# SCH_MCP23017_usb_to_ttl_2021-07-08.net
KiCad netlist of a schematic drawn in EasyEDA
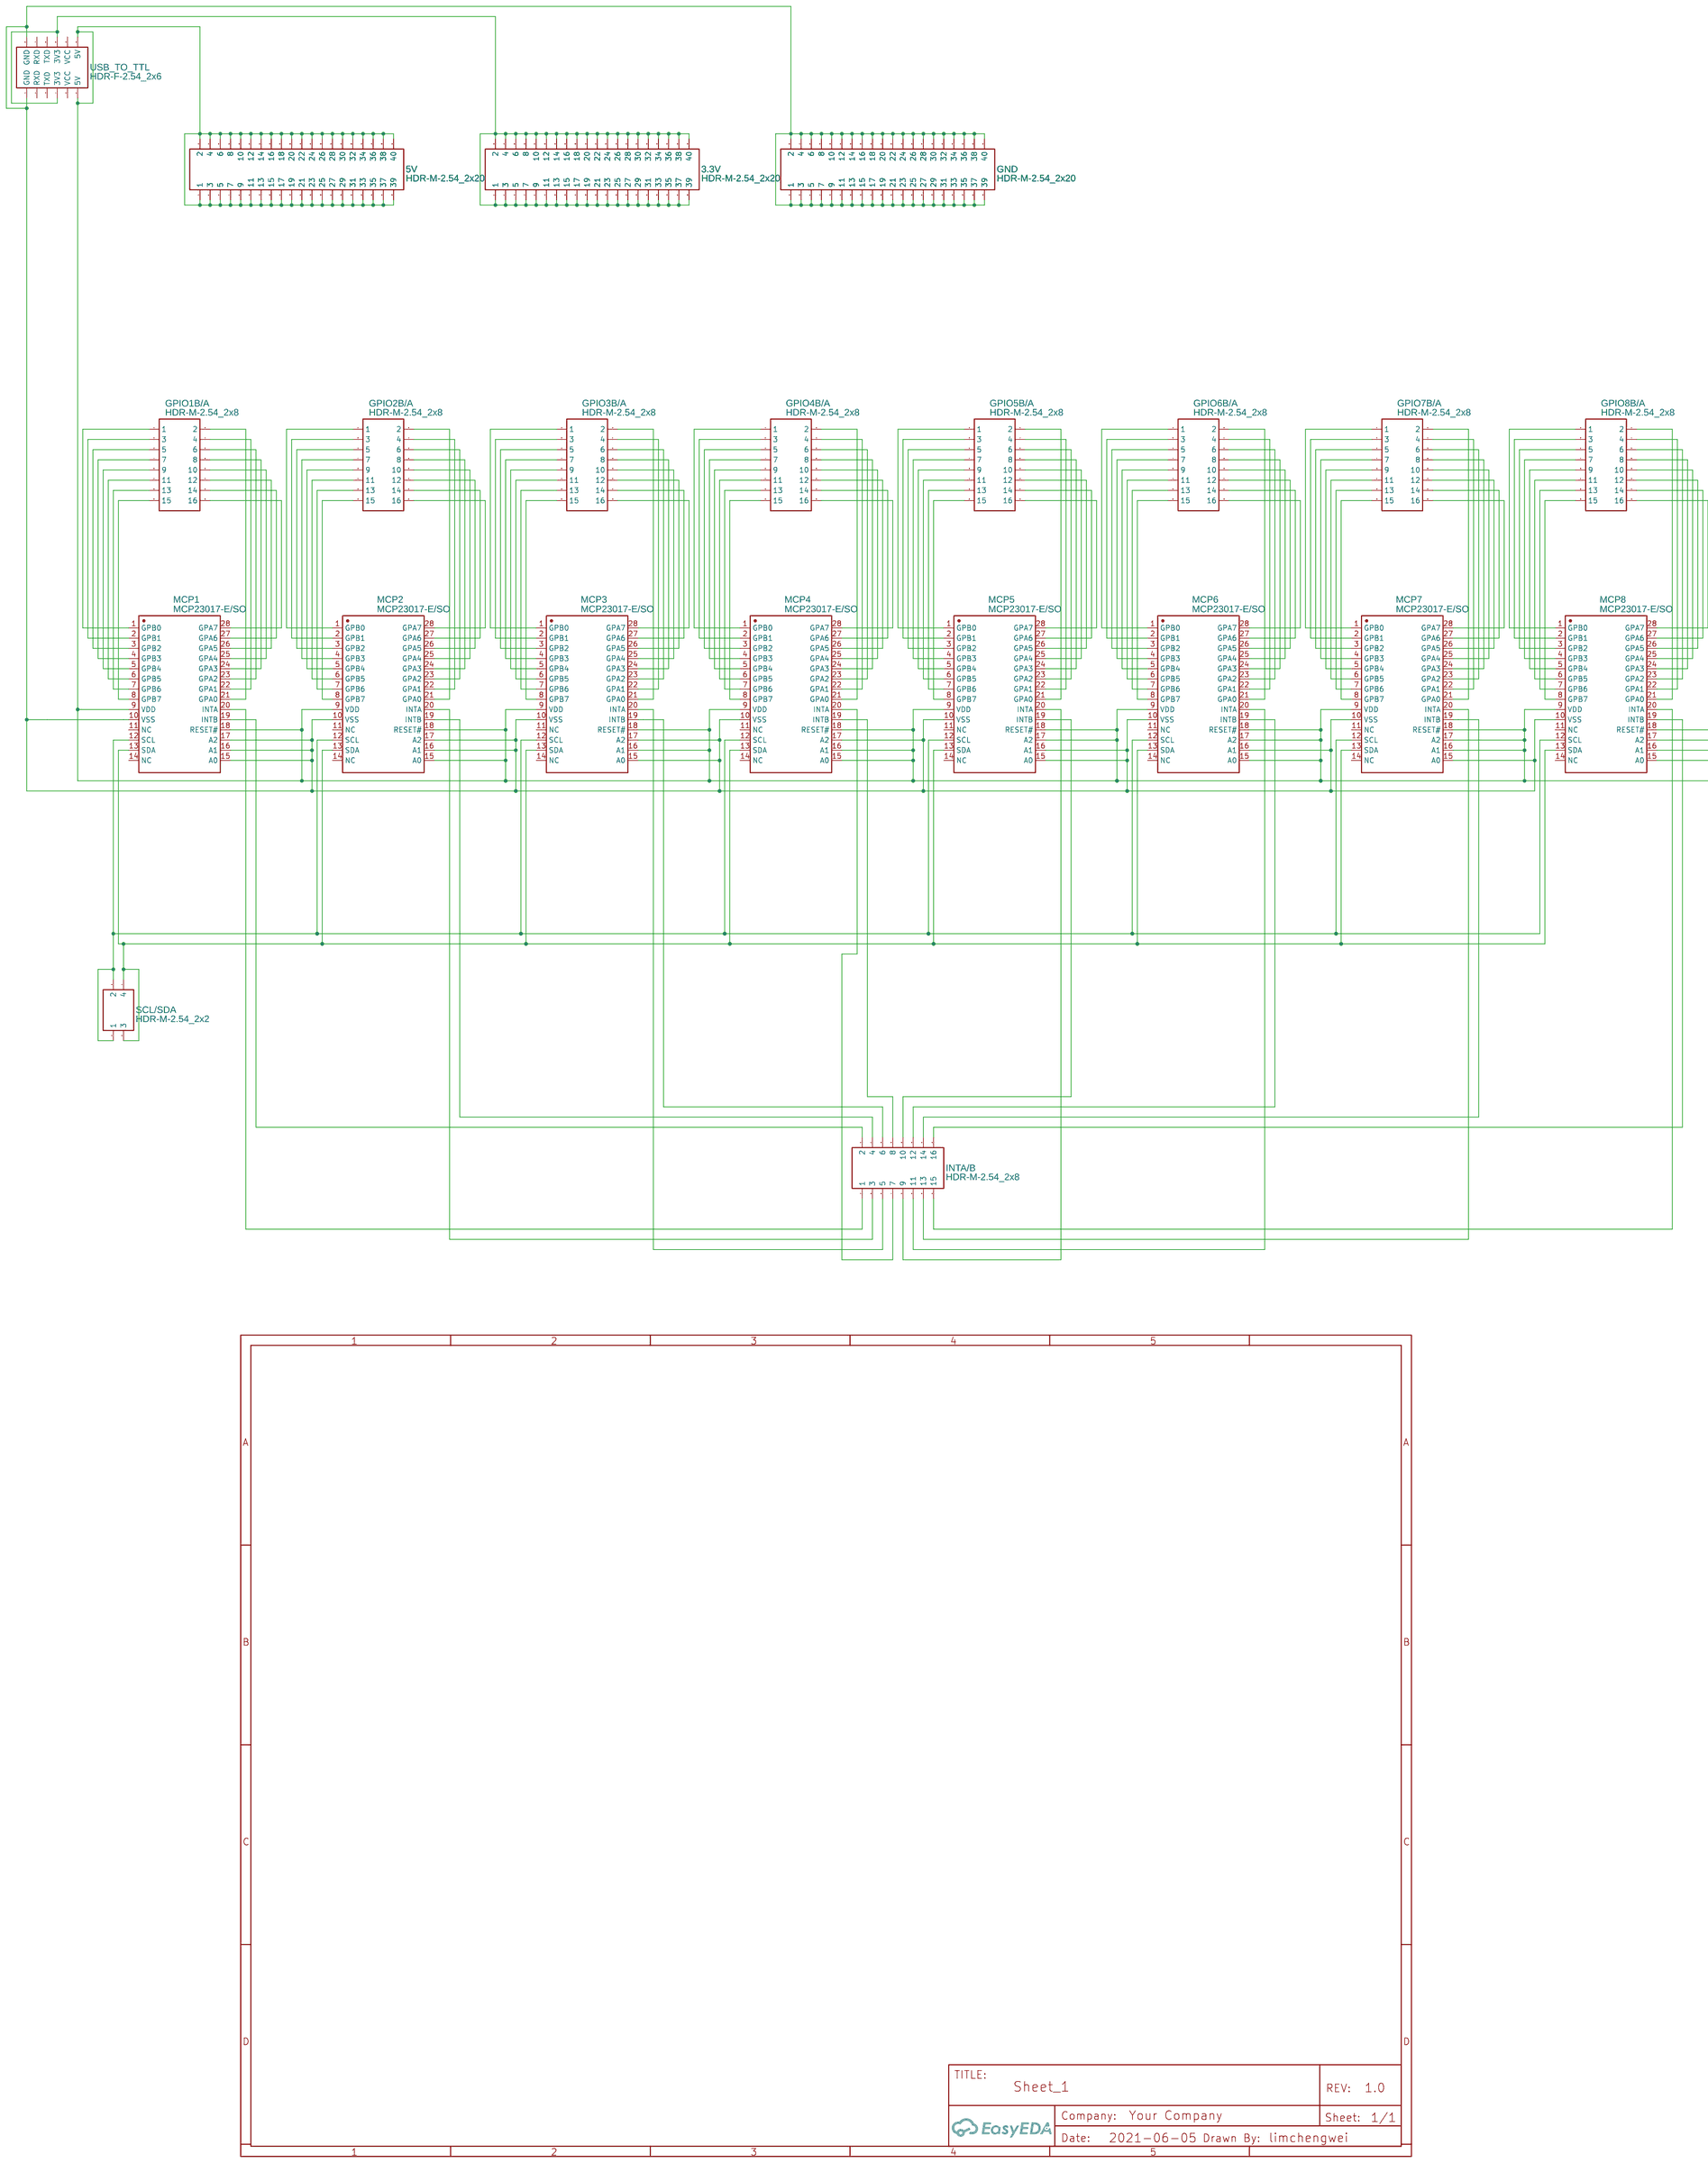
[diagram p0: schematic sheet]

(export (version "E")
  (design (tool "Eeschema 10.0.6"))
  (components
    (comp (ref "3.3V")
      (value "HDR-M-2.54_2x20")
      (fields (field (name "BOM_Supplier Part") "C50980"))
      (libsource (lib "") (part "HDR-M-2.54_2x20"))
    )
    (comp (ref "5V")
      (value "HDR-M-2.54_2x20")
      (fields (field (name "BOM_Supplier Part") "C50980"))
      (libsource (lib "") (part "HDR-M-2.54_2x20_1"))
    )
    (comp (ref "GND")
      (value "HDR-M-2.54_2x20")
      (fields (field (name "BOM_Supplier Part") "C50980"))
      (libsource (lib "") (part "HDR-M-2.54_2x20_2"))
    )
    (comp (ref "GPIO1B/A")
      (value "HDR-M-2.54_2x8")
      (fields (field (name "BOM_Supplier Part") "C68234"))
      (libsource (lib "") (part "HDR-M-2.54_2x8_8"))
    )
    (comp (ref "GPIO2B/A")
      (value "HDR-M-2.54_2x8")
      (fields (field (name "BOM_Supplier Part") "C68234"))
      (libsource (lib "") (part "HDR-M-2.54_2x8_2"))
    )
    (comp (ref "GPIO3B/A")
      (value "HDR-M-2.54_2x8")
      (fields (field (name "BOM_Supplier Part") "C68234"))
      (libsource (lib "") (part "HDR-M-2.54_2x8"))
    )
    (comp (ref "GPIO4B/A")
      (value "HDR-M-2.54_2x8")
      (fields (field (name "BOM_Supplier Part") "C68234"))
      (libsource (lib "") (part "HDR-M-2.54_2x8_4"))
    )
    (comp (ref "GPIO5B/A")
      (value "HDR-M-2.54_2x8")
      (fields (field (name "BOM_Supplier Part") "C68234"))
      (libsource (lib "") (part "HDR-M-2.54_2x8_6"))
    )
    (comp (ref "GPIO6B/A")
      (value "HDR-M-2.54_2x8")
      (fields (field (name "BOM_Supplier Part") "C68234"))
      (libsource (lib "") (part "HDR-M-2.54_2x8_3"))
    )
    (comp (ref "GPIO7B/A")
      (value "HDR-M-2.54_2x8")
      (fields (field (name "BOM_Supplier Part") "C68234"))
      (libsource (lib "") (part "HDR-M-2.54_2x8_5"))
    )
    (comp (ref "GPIO8B/A")
      (value "HDR-M-2.54_2x8")
      (fields (field (name "BOM_Supplier Part") "C68234"))
      (libsource (lib "") (part "HDR-M-2.54_2x8_1"))
    )
    (comp (ref "INTA/B")
      (value "HDR-M-2.54_2x8")
      (fields (field (name "BOM_Supplier Part") "C68234"))
      (libsource (lib "") (part "HDR-M-2.54_2x8_7"))
    )
    (comp (ref "MCP1")
      (value "MCP23017-E/SO")
      (fields (field (name "BOM_Supplier Part") "C47023"))
      (libsource (lib "") (part "MCP23017-E/SO"))
    )
    (comp (ref "MCP2")
      (value "MCP23017-E/SO")
      (fields (field (name "BOM_Supplier Part") "C47023"))
      (libsource (lib "") (part "MCP23017-E/SO"))
    )
    (comp (ref "MCP3")
      (value "MCP23017-E/SO")
      (fields (field (name "BOM_Supplier Part") "C47023"))
      (libsource (lib "") (part "MCP23017-E/SO"))
    )
    (comp (ref "MCP4")
      (value "MCP23017-E/SO")
      (fields (field (name "BOM_Supplier Part") "C47023"))
      (libsource (lib "") (part "MCP23017-E/SO"))
    )
    (comp (ref "MCP5")
      (value "MCP23017-E/SO")
      (fields (field (name "BOM_Supplier Part") "C47023"))
      (libsource (lib "") (part "MCP23017-E/SO"))
    )
    (comp (ref "MCP6")
      (value "MCP23017-E/SO")
      (fields (field (name "BOM_Supplier Part") "C47023"))
      (libsource (lib "") (part "MCP23017-E/SO"))
    )
    (comp (ref "MCP7")
      (value "MCP23017-E/SO")
      (fields (field (name "BOM_Supplier Part") "C47023"))
      (libsource (lib "") (part "MCP23017-E/SO"))
    )
    (comp (ref "MCP8")
      (value "MCP23017-E/SO")
      (fields (field (name "BOM_Supplier Part") "C47023"))
      (libsource (lib "") (part "MCP23017-E/SO"))
    )
    (comp (ref "SCL/SDA")
      (value "HDR-M-2.54_2x2")
      (fields (field (name "BOM_Supplier Part") "C66690"))
      (libsource (lib "") (part "HDR-M-2.54_2x2"))
    )
    (comp (ref "USB_TO_TTL")
      (value "HDR-F-2.54_2x6")
      (fields (field (name "BOM_Supplier Part") "C36191"))
      (libsource (lib "") (part "HDR-F-2.54_2x6"))
    )
  )
  (nets
    (net (code "1") (name "Net-(3.3V-Pad1)") (class "Default")
      (node (ref "3.3V") (pin "1") (pinfunction "1_1") (pintype "input"))
      (node (ref "3.3V") (pin "10") (pinfunction "10_10") (pintype "input"))
      (node (ref "3.3V") (pin "11") (pinfunction "11_11") (pintype "input"))
      (node (ref "3.3V") (pin "12") (pinfunction "12_12") (pintype "input"))
      (node (ref "3.3V") (pin "13") (pinfunction "13_13") (pintype "input"))
      (node (ref "3.3V") (pin "14") (pinfunction "14_14") (pintype "input"))
      (node (ref "3.3V") (pin "15") (pinfunction "15_15") (pintype "input"))
      (node (ref "3.3V") (pin "16") (pinfunction "16_16") (pintype "input"))
      (node (ref "3.3V") (pin "17") (pinfunction "17_17") (pintype "input"))
      (node (ref "3.3V") (pin "18") (pinfunction "18_18") (pintype "input"))
      (node (ref "3.3V") (pin "19") (pinfunction "19_19") (pintype "input"))
      (node (ref "3.3V") (pin "2") (pinfunction "2_2") (pintype "input"))
      (node (ref "3.3V") (pin "20") (pinfunction "20_20") (pintype "input"))
      (node (ref "3.3V") (pin "21") (pinfunction "21_21") (pintype "input"))
      (node (ref "3.3V") (pin "22") (pinfunction "22_22") (pintype "input"))
      (node (ref "3.3V") (pin "23") (pinfunction "23_23") (pintype "input"))
      (node (ref "3.3V") (pin "24") (pinfunction "24_24") (pintype "input"))
      (node (ref "3.3V") (pin "25") (pinfunction "25_25") (pintype "input"))
      (node (ref "3.3V") (pin "26") (pinfunction "26_26") (pintype "input"))
      (node (ref "3.3V") (pin "27") (pinfunction "27_27") (pintype "input"))
      (node (ref "3.3V") (pin "28") (pinfunction "28_28") (pintype "input"))
      (node (ref "3.3V") (pin "29") (pinfunction "29_29") (pintype "input"))
      (node (ref "3.3V") (pin "3") (pinfunction "3_3") (pintype "input"))
      (node (ref "3.3V") (pin "30") (pinfunction "30_30") (pintype "input"))
      (node (ref "3.3V") (pin "31") (pinfunction "31_31") (pintype "input"))
      (node (ref "3.3V") (pin "32") (pinfunction "32_32") (pintype "input"))
      (node (ref "3.3V") (pin "33") (pinfunction "33_33") (pintype "input"))
      (node (ref "3.3V") (pin "34") (pinfunction "34_34") (pintype "input"))
      (node (ref "3.3V") (pin "35") (pinfunction "35_35") (pintype "input"))
      (node (ref "3.3V") (pin "36") (pinfunction "36_36") (pintype "input"))
      (node (ref "3.3V") (pin "37") (pinfunction "37_37") (pintype "input"))
      (node (ref "3.3V") (pin "38") (pinfunction "38_38") (pintype "input"))
      (node (ref "3.3V") (pin "39") (pinfunction "39_39") (pintype "input"))
      (node (ref "3.3V") (pin "4") (pinfunction "4_4") (pintype "input"))
      (node (ref "3.3V") (pin "40") (pinfunction "40_40") (pintype "input"))
      (node (ref "3.3V") (pin "5") (pinfunction "5_5") (pintype "input"))
      (node (ref "3.3V") (pin "6") (pinfunction "6_6") (pintype "input"))
      (node (ref "3.3V") (pin "7") (pinfunction "7_7") (pintype "input"))
      (node (ref "3.3V") (pin "8") (pinfunction "8_8") (pintype "input"))
      (node (ref "3.3V") (pin "9") (pinfunction "9_9") (pintype "input"))
      (node (ref "USB_TO_TTL") (pin "7") (pinfunction "3V3_7") (pintype "input"))
      (node (ref "USB_TO_TTL") (pin "8") (pinfunction "3V3_8") (pintype "input"))
    )
    (net (code "2") (name "Net-(MCP1-A0)") (class "Default")
      (node (ref "GND") (pin "1") (pinfunction "1_1") (pintype "input"))
      (node (ref "GND") (pin "10") (pinfunction "10_10") (pintype "input"))
      (node (ref "GND") (pin "11") (pinfunction "11_11") (pintype "input"))
      (node (ref "GND") (pin "12") (pinfunction "12_12") (pintype "input"))
      (node (ref "GND") (pin "13") (pinfunction "13_13") (pintype "input"))
      (node (ref "GND") (pin "14") (pinfunction "14_14") (pintype "input"))
      (node (ref "GND") (pin "15") (pinfunction "15_15") (pintype "input"))
      (node (ref "GND") (pin "16") (pinfunction "16_16") (pintype "input"))
      (node (ref "GND") (pin "17") (pinfunction "17_17") (pintype "input"))
      (node (ref "GND") (pin "18") (pinfunction "18_18") (pintype "input"))
      (node (ref "GND") (pin "19") (pinfunction "19_19") (pintype "input"))
      (node (ref "GND") (pin "2") (pinfunction "2_2") (pintype "input"))
      (node (ref "GND") (pin "20") (pinfunction "20_20") (pintype "input"))
      (node (ref "GND") (pin "21") (pinfunction "21_21") (pintype "input"))
      (node (ref "GND") (pin "22") (pinfunction "22_22") (pintype "input"))
      (node (ref "GND") (pin "23") (pinfunction "23_23") (pintype "input"))
      (node (ref "GND") (pin "24") (pinfunction "24_24") (pintype "input"))
      (node (ref "GND") (pin "25") (pinfunction "25_25") (pintype "input"))
      (node (ref "GND") (pin "26") (pinfunction "26_26") (pintype "input"))
      (node (ref "GND") (pin "27") (pinfunction "27_27") (pintype "input"))
      (node (ref "GND") (pin "28") (pinfunction "28_28") (pintype "input"))
      (node (ref "GND") (pin "29") (pinfunction "29_29") (pintype "input"))
      (node (ref "GND") (pin "3") (pinfunction "3_3") (pintype "input"))
      (node (ref "GND") (pin "30") (pinfunction "30_30") (pintype "input"))
      (node (ref "GND") (pin "31") (pinfunction "31_31") (pintype "input"))
      (node (ref "GND") (pin "32") (pinfunction "32_32") (pintype "input"))
      (node (ref "GND") (pin "33") (pinfunction "33_33") (pintype "input"))
      (node (ref "GND") (pin "34") (pinfunction "34_34") (pintype "input"))
      (node (ref "GND") (pin "35") (pinfunction "35_35") (pintype "input"))
      (node (ref "GND") (pin "36") (pinfunction "36_36") (pintype "input"))
      (node (ref "GND") (pin "37") (pinfunction "37_37") (pintype "input"))
      (node (ref "GND") (pin "38") (pinfunction "38_38") (pintype "input"))
      (node (ref "GND") (pin "39") (pinfunction "39_39") (pintype "input"))
      (node (ref "GND") (pin "4") (pinfunction "4_4") (pintype "input"))
      (node (ref "GND") (pin "40") (pinfunction "40_40") (pintype "input"))
      (node (ref "GND") (pin "5") (pinfunction "5_5") (pintype "input"))
      (node (ref "GND") (pin "6") (pinfunction "6_6") (pintype "input"))
      (node (ref "GND") (pin "7") (pinfunction "7_7") (pintype "input"))
      (node (ref "GND") (pin "8") (pinfunction "8_8") (pintype "input"))
      (node (ref "GND") (pin "9") (pinfunction "9_9") (pintype "input"))
      (node (ref "MCP1") (pin "10") (pinfunction "VSS_10") (pintype "unspecified"))
      (node (ref "MCP1") (pin "15") (pinfunction "A0_15") (pintype "unspecified"))
      (node (ref "MCP1") (pin "16") (pinfunction "A1_16") (pintype "unspecified"))
      (node (ref "MCP1") (pin "17") (pinfunction "A2_17") (pintype "unspecified"))
      (node (ref "MCP2") (pin "10") (pinfunction "VSS_10") (pintype "unspecified"))
      (node (ref "MCP2") (pin "16") (pinfunction "A1_16") (pintype "unspecified"))
      (node (ref "MCP2") (pin "17") (pinfunction "A2_17") (pintype "unspecified"))
      (node (ref "MCP3") (pin "10") (pinfunction "VSS_10") (pintype "unspecified"))
      (node (ref "MCP3") (pin "15") (pinfunction "A0_15") (pintype "unspecified"))
      (node (ref "MCP3") (pin "17") (pinfunction "A2_17") (pintype "unspecified"))
      (node (ref "MCP4") (pin "10") (pinfunction "VSS_10") (pintype "unspecified"))
      (node (ref "MCP4") (pin "17") (pinfunction "A2_17") (pintype "unspecified"))
      (node (ref "MCP5") (pin "10") (pinfunction "VSS_10") (pintype "unspecified"))
      (node (ref "MCP5") (pin "15") (pinfunction "A0_15") (pintype "unspecified"))
      (node (ref "MCP5") (pin "16") (pinfunction "A1_16") (pintype "unspecified"))
      (node (ref "MCP6") (pin "10") (pinfunction "VSS_10") (pintype "unspecified"))
      (node (ref "MCP6") (pin "16") (pinfunction "A1_16") (pintype "unspecified"))
      (node (ref "MCP7") (pin "10") (pinfunction "VSS_10") (pintype "unspecified"))
      (node (ref "MCP7") (pin "15") (pinfunction "A0_15") (pintype "unspecified"))
      (node (ref "MCP8") (pin "10") (pinfunction "VSS_10") (pintype "unspecified"))
      (node (ref "USB_TO_TTL") (pin "1") (pinfunction "GND_1") (pintype "input"))
      (node (ref "USB_TO_TTL") (pin "2") (pinfunction "GND_2") (pintype "input"))
    )
    (net (code "3") (name "Net-(MCP1-GPA0)") (class "Default")
      (node (ref "GPIO1B/A") (pin "2") (pinfunction "2_2") (pintype "input"))
      (node (ref "MCP1") (pin "21") (pinfunction "GPA0_21") (pintype "unspecified"))
    )
    (net (code "4") (name "Net-(MCP1-GPA1)") (class "Default")
      (node (ref "GPIO1B/A") (pin "4") (pinfunction "4_4") (pintype "input"))
      (node (ref "MCP1") (pin "22") (pinfunction "GPA1_22") (pintype "unspecified"))
    )
    (net (code "5") (name "Net-(MCP1-GPA2)") (class "Default")
      (node (ref "GPIO1B/A") (pin "6") (pinfunction "6_6") (pintype "input"))
      (node (ref "MCP1") (pin "23") (pinfunction "GPA2_23") (pintype "unspecified"))
    )
    (net (code "6") (name "Net-(MCP1-GPA3)") (class "Default")
      (node (ref "GPIO1B/A") (pin "8") (pinfunction "8_8") (pintype "input"))
      (node (ref "MCP1") (pin "24") (pinfunction "GPA3_24") (pintype "unspecified"))
    )
    (net (code "7") (name "Net-(MCP1-GPA4)") (class "Default")
      (node (ref "GPIO1B/A") (pin "10") (pinfunction "10_10") (pintype "input"))
      (node (ref "MCP1") (pin "25") (pinfunction "GPA4_25") (pintype "unspecified"))
    )
    (net (code "8") (name "Net-(MCP1-GPA5)") (class "Default")
      (node (ref "GPIO1B/A") (pin "12") (pinfunction "12_12") (pintype "input"))
      (node (ref "MCP1") (pin "26") (pinfunction "GPA5_26") (pintype "unspecified"))
    )
    (net (code "9") (name "Net-(MCP1-GPA6)") (class "Default")
      (node (ref "GPIO1B/A") (pin "14") (pinfunction "14_14") (pintype "input"))
      (node (ref "MCP1") (pin "27") (pinfunction "GPA6_27") (pintype "unspecified"))
    )
    (net (code "10") (name "Net-(MCP1-GPA7)") (class "Default")
      (node (ref "GPIO1B/A") (pin "16") (pinfunction "16_16") (pintype "input"))
      (node (ref "MCP1") (pin "28") (pinfunction "GPA7_28") (pintype "unspecified"))
    )
    (net (code "11") (name "Net-(MCP1-GPB0)") (class "Default")
      (node (ref "GPIO1B/A") (pin "1") (pinfunction "1_1") (pintype "input"))
      (node (ref "MCP1") (pin "1") (pinfunction "GPB0_1") (pintype "unspecified"))
    )
    (net (code "12") (name "Net-(MCP1-GPB1)") (class "Default")
      (node (ref "GPIO1B/A") (pin "3") (pinfunction "3_3") (pintype "input"))
      (node (ref "MCP1") (pin "2") (pinfunction "GPB1_2") (pintype "unspecified"))
    )
    (net (code "13") (name "Net-(MCP1-GPB2)") (class "Default")
      (node (ref "GPIO1B/A") (pin "5") (pinfunction "5_5") (pintype "input"))
      (node (ref "MCP1") (pin "3") (pinfunction "GPB2_3") (pintype "unspecified"))
    )
    (net (code "14") (name "Net-(MCP1-GPB3)") (class "Default")
      (node (ref "GPIO1B/A") (pin "7") (pinfunction "7_7") (pintype "input"))
      (node (ref "MCP1") (pin "4") (pinfunction "GPB3_4") (pintype "unspecified"))
    )
    (net (code "15") (name "Net-(MCP1-GPB4)") (class "Default")
      (node (ref "GPIO1B/A") (pin "9") (pinfunction "9_9") (pintype "input"))
      (node (ref "MCP1") (pin "5") (pinfunction "GPB4_5") (pintype "unspecified"))
    )
    (net (code "16") (name "Net-(MCP1-GPB5)") (class "Default")
      (node (ref "GPIO1B/A") (pin "11") (pinfunction "11_11") (pintype "input"))
      (node (ref "MCP1") (pin "6") (pinfunction "GPB5_6") (pintype "unspecified"))
    )
    (net (code "17") (name "Net-(MCP1-GPB6)") (class "Default")
      (node (ref "GPIO1B/A") (pin "13") (pinfunction "13_13") (pintype "input"))
      (node (ref "MCP1") (pin "7") (pinfunction "GPB6_7") (pintype "unspecified"))
    )
    (net (code "18") (name "Net-(MCP1-GPB7)") (class "Default")
      (node (ref "GPIO1B/A") (pin "15") (pinfunction "15_15") (pintype "input"))
      (node (ref "MCP1") (pin "8") (pinfunction "GPB7_8") (pintype "unspecified"))
    )
    (net (code "19") (name "Net-(MCP1-INTA)") (class "Default")
      (node (ref "INTA/B") (pin "1") (pinfunction "1_1") (pintype "input"))
      (node (ref "MCP1") (pin "20") (pinfunction "INTA_20") (pintype "unspecified"))
    )
    (net (code "20") (name "Net-(MCP1-INTB)") (class "Default")
      (node (ref "INTA/B") (pin "2") (pinfunction "2_2") (pintype "input"))
      (node (ref "MCP1") (pin "19") (pinfunction "INTB_19") (pintype "unspecified"))
    )
    (net (code "21") (name "Net-(MCP1-RESET#)") (class "Default")
      (node (ref "5V") (pin "1") (pinfunction "1_1") (pintype "input"))
      (node (ref "5V") (pin "10") (pinfunction "10_10") (pintype "input"))
      (node (ref "5V") (pin "11") (pinfunction "11_11") (pintype "input"))
      (node (ref "5V") (pin "12") (pinfunction "12_12") (pintype "input"))
      (node (ref "5V") (pin "13") (pinfunction "13_13") (pintype "input"))
      (node (ref "5V") (pin "14") (pinfunction "14_14") (pintype "input"))
      (node (ref "5V") (pin "15") (pinfunction "15_15") (pintype "input"))
      (node (ref "5V") (pin "16") (pinfunction "16_16") (pintype "input"))
      (node (ref "5V") (pin "17") (pinfunction "17_17") (pintype "input"))
      (node (ref "5V") (pin "18") (pinfunction "18_18") (pintype "input"))
      (node (ref "5V") (pin "19") (pinfunction "19_19") (pintype "input"))
      (node (ref "5V") (pin "2") (pinfunction "2_2") (pintype "input"))
      (node (ref "5V") (pin "20") (pinfunction "20_20") (pintype "input"))
      (node (ref "5V") (pin "21") (pinfunction "21_21") (pintype "input"))
      (node (ref "5V") (pin "22") (pinfunction "22_22") (pintype "input"))
      (node (ref "5V") (pin "23") (pinfunction "23_23") (pintype "input"))
      (node (ref "5V") (pin "24") (pinfunction "24_24") (pintype "input"))
      (node (ref "5V") (pin "25") (pinfunction "25_25") (pintype "input"))
      (node (ref "5V") (pin "26") (pinfunction "26_26") (pintype "input"))
      (node (ref "5V") (pin "27") (pinfunction "27_27") (pintype "input"))
      (node (ref "5V") (pin "28") (pinfunction "28_28") (pintype "input"))
      (node (ref "5V") (pin "29") (pinfunction "29_29") (pintype "input"))
      (node (ref "5V") (pin "3") (pinfunction "3_3") (pintype "input"))
      (node (ref "5V") (pin "30") (pinfunction "30_30") (pintype "input"))
      (node (ref "5V") (pin "31") (pinfunction "31_31") (pintype "input"))
      (node (ref "5V") (pin "32") (pinfunction "32_32") (pintype "input"))
      (node (ref "5V") (pin "33") (pinfunction "33_33") (pintype "input"))
      (node (ref "5V") (pin "34") (pinfunction "34_34") (pintype "input"))
      (node (ref "5V") (pin "35") (pinfunction "35_35") (pintype "input"))
      (node (ref "5V") (pin "36") (pinfunction "36_36") (pintype "input"))
      (node (ref "5V") (pin "37") (pinfunction "37_37") (pintype "input"))
      (node (ref "5V") (pin "38") (pinfunction "38_38") (pintype "input"))
      (node (ref "5V") (pin "39") (pinfunction "39_39") (pintype "input"))
      (node (ref "5V") (pin "4") (pinfunction "4_4") (pintype "input"))
      (node (ref "5V") (pin "40") (pinfunction "40_40") (pintype "input"))
      (node (ref "5V") (pin "5") (pinfunction "5_5") (pintype "input"))
      (node (ref "5V") (pin "6") (pinfunction "6_6") (pintype "input"))
      (node (ref "5V") (pin "7") (pinfunction "7_7") (pintype "input"))
      (node (ref "5V") (pin "8") (pinfunction "8_8") (pintype "input"))
      (node (ref "5V") (pin "9") (pinfunction "9_9") (pintype "input"))
      (node (ref "MCP1") (pin "18") (pinfunction "RESET#_18") (pintype "unspecified"))
      (node (ref "MCP1") (pin "9") (pinfunction "VDD_9") (pintype "unspecified"))
      (node (ref "MCP2") (pin "15") (pinfunction "A0_15") (pintype "unspecified"))
      (node (ref "MCP2") (pin "18") (pinfunction "RESET#_18") (pintype "unspecified"))
      (node (ref "MCP2") (pin "9") (pinfunction "VDD_9") (pintype "unspecified"))
      (node (ref "MCP3") (pin "16") (pinfunction "A1_16") (pintype "unspecified"))
      (node (ref "MCP3") (pin "18") (pinfunction "RESET#_18") (pintype "unspecified"))
      (node (ref "MCP3") (pin "9") (pinfunction "VDD_9") (pintype "unspecified"))
      (node (ref "MCP4") (pin "15") (pinfunction "A0_15") (pintype "unspecified"))
      (node (ref "MCP4") (pin "16") (pinfunction "A1_16") (pintype "unspecified"))
      (node (ref "MCP4") (pin "18") (pinfunction "RESET#_18") (pintype "unspecified"))
      (node (ref "MCP4") (pin "9") (pinfunction "VDD_9") (pintype "unspecified"))
      (node (ref "MCP5") (pin "17") (pinfunction "A2_17") (pintype "unspecified"))
      (node (ref "MCP5") (pin "18") (pinfunction "RESET#_18") (pintype "unspecified"))
      (node (ref "MCP5") (pin "9") (pinfunction "VDD_9") (pintype "unspecified"))
      (node (ref "MCP6") (pin "15") (pinfunction "A0_15") (pintype "unspecified"))
      (node (ref "MCP6") (pin "17") (pinfunction "A2_17") (pintype "unspecified"))
      (node (ref "MCP6") (pin "18") (pinfunction "RESET#_18") (pintype "unspecified"))
      (node (ref "MCP6") (pin "9") (pinfunction "VDD_9") (pintype "unspecified"))
      (node (ref "MCP7") (pin "16") (pinfunction "A1_16") (pintype "unspecified"))
      (node (ref "MCP7") (pin "17") (pinfunction "A2_17") (pintype "unspecified"))
      (node (ref "MCP7") (pin "18") (pinfunction "RESET#_18") (pintype "unspecified"))
      (node (ref "MCP7") (pin "9") (pinfunction "VDD_9") (pintype "unspecified"))
      (node (ref "MCP8") (pin "15") (pinfunction "A0_15") (pintype "unspecified"))
      (node (ref "MCP8") (pin "16") (pinfunction "A1_16") (pintype "unspecified"))
      (node (ref "MCP8") (pin "17") (pinfunction "A2_17") (pintype "unspecified"))
      (node (ref "MCP8") (pin "18") (pinfunction "RESET#_18") (pintype "unspecified"))
      (node (ref "MCP8") (pin "9") (pinfunction "VDD_9") (pintype "unspecified"))
      (node (ref "USB_TO_TTL") (pin "11") (pinfunction "5V_11") (pintype "input"))
      (node (ref "USB_TO_TTL") (pin "12") (pinfunction "5V_12") (pintype "input"))
    )
    (net (code "22") (name "Net-(MCP1-SCL)") (class "Default")
      (node (ref "MCP1") (pin "12") (pinfunction "SCL_12") (pintype "unspecified"))
      (node (ref "MCP2") (pin "12") (pinfunction "SCL_12") (pintype "unspecified"))
      (node (ref "MCP3") (pin "12") (pinfunction "SCL_12") (pintype "unspecified"))
      (node (ref "MCP4") (pin "12") (pinfunction "SCL_12") (pintype "unspecified"))
      (node (ref "MCP5") (pin "12") (pinfunction "SCL_12") (pintype "unspecified"))
      (node (ref "MCP6") (pin "12") (pinfunction "SCL_12") (pintype "unspecified"))
      (node (ref "MCP7") (pin "12") (pinfunction "SCL_12") (pintype "unspecified"))
      (node (ref "MCP8") (pin "12") (pinfunction "SCL_12") (pintype "unspecified"))
      (node (ref "SCL/SDA") (pin "1") (pinfunction "1_1") (pintype "input"))
      (node (ref "SCL/SDA") (pin "2") (pinfunction "2_2") (pintype "input"))
    )
    (net (code "23") (name "Net-(MCP1-SDA)") (class "Default")
      (node (ref "MCP1") (pin "13") (pinfunction "SDA_13") (pintype "unspecified"))
      (node (ref "MCP2") (pin "13") (pinfunction "SDA_13") (pintype "unspecified"))
      (node (ref "MCP3") (pin "13") (pinfunction "SDA_13") (pintype "unspecified"))
      (node (ref "MCP4") (pin "13") (pinfunction "SDA_13") (pintype "unspecified"))
      (node (ref "MCP5") (pin "13") (pinfunction "SDA_13") (pintype "unspecified"))
      (node (ref "MCP6") (pin "13") (pinfunction "SDA_13") (pintype "unspecified"))
      (node (ref "MCP7") (pin "13") (pinfunction "SDA_13") (pintype "unspecified"))
      (node (ref "MCP8") (pin "13") (pinfunction "SDA_13") (pintype "unspecified"))
      (node (ref "SCL/SDA") (pin "3") (pinfunction "3_3") (pintype "input"))
      (node (ref "SCL/SDA") (pin "4") (pinfunction "4_4") (pintype "input"))
    )
    (net (code "24") (name "Net-(MCP2-GPA0)") (class "Default")
      (node (ref "GPIO2B/A") (pin "2") (pinfunction "2_2") (pintype "input"))
      (node (ref "MCP2") (pin "21") (pinfunction "GPA0_21") (pintype "unspecified"))
    )
    (net (code "25") (name "Net-(MCP2-GPA1)") (class "Default")
      (node (ref "GPIO2B/A") (pin "4") (pinfunction "4_4") (pintype "input"))
      (node (ref "MCP2") (pin "22") (pinfunction "GPA1_22") (pintype "unspecified"))
    )
    (net (code "26") (name "Net-(MCP2-GPA2)") (class "Default")
      (node (ref "GPIO2B/A") (pin "6") (pinfunction "6_6") (pintype "input"))
      (node (ref "MCP2") (pin "23") (pinfunction "GPA2_23") (pintype "unspecified"))
    )
    (net (code "27") (name "Net-(MCP2-GPA3)") (class "Default")
      (node (ref "GPIO2B/A") (pin "8") (pinfunction "8_8") (pintype "input"))
      (node (ref "MCP2") (pin "24") (pinfunction "GPA3_24") (pintype "unspecified"))
    )
    (net (code "28") (name "Net-(MCP2-GPA4)") (class "Default")
      (node (ref "GPIO2B/A") (pin "10") (pinfunction "10_10") (pintype "input"))
      (node (ref "MCP2") (pin "25") (pinfunction "GPA4_25") (pintype "unspecified"))
    )
    (net (code "29") (name "Net-(MCP2-GPA5)") (class "Default")
      (node (ref "GPIO2B/A") (pin "12") (pinfunction "12_12") (pintype "input"))
      (node (ref "MCP2") (pin "26") (pinfunction "GPA5_26") (pintype "unspecified"))
    )
    (net (code "30") (name "Net-(MCP2-GPA6)") (class "Default")
      (node (ref "GPIO2B/A") (pin "14") (pinfunction "14_14") (pintype "input"))
      (node (ref "MCP2") (pin "27") (pinfunction "GPA6_27") (pintype "unspecified"))
    )
    (net (code "31") (name "Net-(MCP2-GPA7)") (class "Default")
      (node (ref "GPIO2B/A") (pin "16") (pinfunction "16_16") (pintype "input"))
      (node (ref "MCP2") (pin "28") (pinfunction "GPA7_28") (pintype "unspecified"))
    )
    (net (code "32") (name "Net-(MCP2-GPB0)") (class "Default")
      (node (ref "GPIO2B/A") (pin "1") (pinfunction "1_1") (pintype "input"))
      (node (ref "MCP2") (pin "1") (pinfunction "GPB0_1") (pintype "unspecified"))
    )
    (net (code "33") (name "Net-(MCP2-GPB1)") (class "Default")
      (node (ref "GPIO2B/A") (pin "3") (pinfunction "3_3") (pintype "input"))
      (node (ref "MCP2") (pin "2") (pinfunction "GPB1_2") (pintype "unspecified"))
    )
    (net (code "34") (name "Net-(MCP2-GPB2)") (class "Default")
      (node (ref "GPIO2B/A") (pin "5") (pinfunction "5_5") (pintype "input"))
      (node (ref "MCP2") (pin "3") (pinfunction "GPB2_3") (pintype "unspecified"))
    )
    (net (code "35") (name "Net-(MCP2-GPB3)") (class "Default")
      (node (ref "GPIO2B/A") (pin "7") (pinfunction "7_7") (pintype "input"))
      (node (ref "MCP2") (pin "4") (pinfunction "GPB3_4") (pintype "unspecified"))
    )
    (net (code "36") (name "Net-(MCP2-GPB4)") (class "Default")
      (node (ref "GPIO2B/A") (pin "9") (pinfunction "9_9") (pintype "input"))
      (node (ref "MCP2") (pin "5") (pinfunction "GPB4_5") (pintype "unspecified"))
    )
    (net (code "37") (name "Net-(MCP2-GPB5)") (class "Default")
      (node (ref "GPIO2B/A") (pin "11") (pinfunction "11_11") (pintype "input"))
      (node (ref "MCP2") (pin "6") (pinfunction "GPB5_6") (pintype "unspecified"))
    )
    (net (code "38") (name "Net-(MCP2-GPB6)") (class "Default")
      (node (ref "GPIO2B/A") (pin "13") (pinfunction "13_13") (pintype "input"))
      (node (ref "MCP2") (pin "7") (pinfunction "GPB6_7") (pintype "unspecified"))
    )
    (net (code "39") (name "Net-(MCP2-GPB7)") (class "Default")
      (node (ref "GPIO2B/A") (pin "15") (pinfunction "15_15") (pintype "input"))
      (node (ref "MCP2") (pin "8") (pinfunction "GPB7_8") (pintype "unspecified"))
    )
    (net (code "40") (name "Net-(MCP2-INTA)") (class "Default")
      (node (ref "INTA/B") (pin "3") (pinfunction "3_3") (pintype "input"))
      (node (ref "MCP2") (pin "20") (pinfunction "INTA_20") (pintype "unspecified"))
    )
    (net (code "41") (name "Net-(MCP2-INTB)") (class "Default")
      (node (ref "INTA/B") (pin "4") (pinfunction "4_4") (pintype "input"))
      (node (ref "MCP2") (pin "19") (pinfunction "INTB_19") (pintype "unspecified"))
    )
    (net (code "42") (name "Net-(MCP3-GPA0)") (class "Default")
      (node (ref "GPIO3B/A") (pin "2") (pinfunction "2_2") (pintype "input"))
      (node (ref "MCP3") (pin "21") (pinfunction "GPA0_21") (pintype "unspecified"))
    )
    (net (code "43") (name "Net-(MCP3-GPA1)") (class "Default")
      (node (ref "GPIO3B/A") (pin "4") (pinfunction "4_4") (pintype "input"))
      (node (ref "MCP3") (pin "22") (pinfunction "GPA1_22") (pintype "unspecified"))
    )
    (net (code "44") (name "Net-(MCP3-GPA2)") (class "Default")
      (node (ref "GPIO3B/A") (pin "6") (pinfunction "6_6") (pintype "input"))
      (node (ref "MCP3") (pin "23") (pinfunction "GPA2_23") (pintype "unspecified"))
    )
    (net (code "45") (name "Net-(MCP3-GPA3)") (class "Default")
      (node (ref "GPIO3B/A") (pin "8") (pinfunction "8_8") (pintype "input"))
      (node (ref "MCP3") (pin "24") (pinfunction "GPA3_24") (pintype "unspecified"))
    )
    (net (code "46") (name "Net-(MCP3-GPA4)") (class "Default")
      (node (ref "GPIO3B/A") (pin "10") (pinfunction "10_10") (pintype "input"))
      (node (ref "MCP3") (pin "25") (pinfunction "GPA4_25") (pintype "unspecified"))
    )
    (net (code "47") (name "Net-(MCP3-GPA5)") (class "Default")
      (node (ref "GPIO3B/A") (pin "12") (pinfunction "12_12") (pintype "input"))
      (node (ref "MCP3") (pin "26") (pinfunction "GPA5_26") (pintype "unspecified"))
    )
    (net (code "48") (name "Net-(MCP3-GPA6)") (class "Default")
      (node (ref "GPIO3B/A") (pin "14") (pinfunction "14_14") (pintype "input"))
      (node (ref "MCP3") (pin "27") (pinfunction "GPA6_27") (pintype "unspecified"))
    )
    (net (code "49") (name "Net-(MCP3-GPA7)") (class "Default")
      (node (ref "GPIO3B/A") (pin "16") (pinfunction "16_16") (pintype "input"))
      (node (ref "MCP3") (pin "28") (pinfunction "GPA7_28") (pintype "unspecified"))
    )
    (net (code "50") (name "Net-(MCP3-GPB0)") (class "Default")
      (node (ref "GPIO3B/A") (pin "1") (pinfunction "1_1") (pintype "input"))
      (node (ref "MCP3") (pin "1") (pinfunction "GPB0_1") (pintype "unspecified"))
    )
    (net (code "51") (name "Net-(MCP3-GPB1)") (class "Default")
      (node (ref "GPIO3B/A") (pin "3") (pinfunction "3_3") (pintype "input"))
      (node (ref "MCP3") (pin "2") (pinfunction "GPB1_2") (pintype "unspecified"))
    )
    (net (code "52") (name "Net-(MCP3-GPB2)") (class "Default")
      (node (ref "GPIO3B/A") (pin "5") (pinfunction "5_5") (pintype "input"))
      (node (ref "MCP3") (pin "3") (pinfunction "GPB2_3") (pintype "unspecified"))
    )
    (net (code "53") (name "Net-(MCP3-GPB3)") (class "Default")
      (node (ref "GPIO3B/A") (pin "7") (pinfunction "7_7") (pintype "input"))
      (node (ref "MCP3") (pin "4") (pinfunction "GPB3_4") (pintype "unspecified"))
    )
    (net (code "54") (name "Net-(MCP3-GPB4)") (class "Default")
      (node (ref "GPIO3B/A") (pin "9") (pinfunction "9_9") (pintype "input"))
      (node (ref "MCP3") (pin "5") (pinfunction "GPB4_5") (pintype "unspecified"))
    )
    (net (code "55") (name "Net-(MCP3-GPB5)") (class "Default")
      (node (ref "GPIO3B/A") (pin "11") (pinfunction "11_11") (pintype "input"))
      (node (ref "MCP3") (pin "6") (pinfunction "GPB5_6") (pintype "unspecified"))
    )
    (net (code "56") (name "Net-(MCP3-GPB6)") (class "Default")
      (node (ref "GPIO3B/A") (pin "13") (pinfunction "13_13") (pintype "input"))
      (node (ref "MCP3") (pin "7") (pinfunction "GPB6_7") (pintype "unspecified"))
    )
    (net (code "57") (name "Net-(MCP3-GPB7)") (class "Default")
      (node (ref "GPIO3B/A") (pin "15") (pinfunction "15_15") (pintype "input"))
      (node (ref "MCP3") (pin "8") (pinfunction "GPB7_8") (pintype "unspecified"))
    )
    (net (code "58") (name "Net-(MCP3-INTA)") (class "Default")
      (node (ref "INTA/B") (pin "5") (pinfunction "5_5") (pintype "input"))
      (node (ref "MCP3") (pin "20") (pinfunction "INTA_20") (pintype "unspecified"))
    )
    (net (code "59") (name "Net-(MCP3-INTB)") (class "Default")
      (node (ref "INTA/B") (pin "6") (pinfunction "6_6") (pintype "input"))
      (node (ref "MCP3") (pin "19") (pinfunction "INTB_19") (pintype "unspecified"))
    )
    (net (code "60") (name "Net-(MCP4-GPA0)") (class "Default")
      (node (ref "GPIO4B/A") (pin "2") (pinfunction "2_2") (pintype "input"))
      (node (ref "MCP4") (pin "21") (pinfunction "GPA0_21") (pintype "unspecified"))
    )
    (net (code "61") (name "Net-(MCP4-GPA1)") (class "Default")
      (node (ref "GPIO4B/A") (pin "4") (pinfunction "4_4") (pintype "input"))
      (node (ref "MCP4") (pin "22") (pinfunction "GPA1_22") (pintype "unspecified"))
    )
    (net (code "62") (name "Net-(MCP4-GPA2)") (class "Default")
      (node (ref "GPIO4B/A") (pin "6") (pinfunction "6_6") (pintype "input"))
      (node (ref "MCP4") (pin "23") (pinfunction "GPA2_23") (pintype "unspecified"))
    )
    (net (code "63") (name "Net-(MCP4-GPA3)") (class "Default")
      (node (ref "GPIO4B/A") (pin "8") (pinfunction "8_8") (pintype "input"))
      (node (ref "MCP4") (pin "24") (pinfunction "GPA3_24") (pintype "unspecified"))
    )
    (net (code "64") (name "Net-(MCP4-GPA4)") (class "Default")
      (node (ref "GPIO4B/A") (pin "10") (pinfunction "10_10") (pintype "input"))
      (node (ref "MCP4") (pin "25") (pinfunction "GPA4_25") (pintype "unspecified"))
    )
    (net (code "65") (name "Net-(MCP4-GPA5)") (class "Default")
      (node (ref "GPIO4B/A") (pin "12") (pinfunction "12_12") (pintype "input"))
      (node (ref "MCP4") (pin "26") (pinfunction "GPA5_26") (pintype "unspecified"))
    )
    (net (code "66") (name "Net-(MCP4-GPA6)") (class "Default")
      (node (ref "GPIO4B/A") (pin "14") (pinfunction "14_14") (pintype "input"))
      (node (ref "MCP4") (pin "27") (pinfunction "GPA6_27") (pintype "unspecified"))
    )
    (net (code "67") (name "Net-(MCP4-GPA7)") (class "Default")
      (node (ref "GPIO4B/A") (pin "16") (pinfunction "16_16") (pintype "input"))
      (node (ref "MCP4") (pin "28") (pinfunction "GPA7_28") (pintype "unspecified"))
    )
    (net (code "68") (name "Net-(MCP4-GPB0)") (class "Default")
      (node (ref "GPIO4B/A") (pin "1") (pinfunction "1_1") (pintype "input"))
      (node (ref "MCP4") (pin "1") (pinfunction "GPB0_1") (pintype "unspecified"))
    )
    (net (code "69") (name "Net-(MCP4-GPB1)") (class "Default")
      (node (ref "GPIO4B/A") (pin "3") (pinfunction "3_3") (pintype "input"))
      (node (ref "MCP4") (pin "2") (pinfunction "GPB1_2") (pintype "unspecified"))
    )
    (net (code "70") (name "Net-(MCP4-GPB2)") (class "Default")
      (node (ref "GPIO4B/A") (pin "5") (pinfunction "5_5") (pintype "input"))
      (node (ref "MCP4") (pin "3") (pinfunction "GPB2_3") (pintype "unspecified"))
    )
    (net (code "71") (name "Net-(MCP4-GPB3)") (class "Default")
      (node (ref "GPIO4B/A") (pin "7") (pinfunction "7_7") (pintype "input"))
      (node (ref "MCP4") (pin "4") (pinfunction "GPB3_4") (pintype "unspecified"))
    )
    (net (code "72") (name "Net-(MCP4-GPB4)") (class "Default")
      (node (ref "GPIO4B/A") (pin "9") (pinfunction "9_9") (pintype "input"))
      (node (ref "MCP4") (pin "5") (pinfunction "GPB4_5") (pintype "unspecified"))
    )
    (net (code "73") (name "Net-(MCP4-GPB5)") (class "Default")
      (node (ref "GPIO4B/A") (pin "11") (pinfunction "11_11") (pintype "input"))
      (node (ref "MCP4") (pin "6") (pinfunction "GPB5_6") (pintype "unspecified"))
    )
    (net (code "74") (name "Net-(MCP4-GPB6)") (class "Default")
      (node (ref "GPIO4B/A") (pin "13") (pinfunction "13_13") (pintype "input"))
      (node (ref "MCP4") (pin "7") (pinfunction "GPB6_7") (pintype "unspecified"))
    )
    (net (code "75") (name "Net-(MCP4-GPB7)") (class "Default")
      (node (ref "GPIO4B/A") (pin "15") (pinfunction "15_15") (pintype "input"))
      (node (ref "MCP4") (pin "8") (pinfunction "GPB7_8") (pintype "unspecified"))
    )
    (net (code "76") (name "Net-(MCP4-INTA)") (class "Default")
      (node (ref "INTA/B") (pin "7") (pinfunction "7_7") (pintype "input"))
      (node (ref "MCP4") (pin "20") (pinfunction "INTA_20") (pintype "unspecified"))
    )
    (net (code "77") (name "Net-(MCP4-INTB)") (class "Default")
      (node (ref "INTA/B") (pin "8") (pinfunction "8_8") (pintype "input"))
      (node (ref "MCP4") (pin "19") (pinfunction "INTB_19") (pintype "unspecified"))
    )
    (net (code "78") (name "Net-(MCP5-GPA0)") (class "Default")
      (node (ref "GPIO5B/A") (pin "2") (pinfunction "2_2") (pintype "input"))
      (node (ref "MCP5") (pin "21") (pinfunction "GPA0_21") (pintype "unspecified"))
    )
    (net (code "79") (name "Net-(MCP5-GPA1)") (class "Default")
      (node (ref "GPIO5B/A") (pin "4") (pinfunction "4_4") (pintype "input"))
      (node (ref "MCP5") (pin "22") (pinfunction "GPA1_22") (pintype "unspecified"))
    )
    (net (code "80") (name "Net-(MCP5-GPA2)") (class "Default")
      (node (ref "GPIO5B/A") (pin "6") (pinfunction "6_6") (pintype "input"))
      (node (ref "MCP5") (pin "23") (pinfunction "GPA2_23") (pintype "unspecified"))
    )
    (net (code "81") (name "Net-(MCP5-GPA3)") (class "Default")
      (node (ref "GPIO5B/A") (pin "8") (pinfunction "8_8") (pintype "input"))
      (node (ref "MCP5") (pin "24") (pinfunction "GPA3_24") (pintype "unspecified"))
    )
    (net (code "82") (name "Net-(MCP5-GPA4)") (class "Default")
      (node (ref "GPIO5B/A") (pin "10") (pinfunction "10_10") (pintype "input"))
      (node (ref "MCP5") (pin "25") (pinfunction "GPA4_25") (pintype "unspecified"))
    )
    (net (code "83") (name "Net-(MCP5-GPA5)") (class "Default")
      (node (ref "GPIO5B/A") (pin "12") (pinfunction "12_12") (pintype "input"))
      (node (ref "MCP5") (pin "26") (pinfunction "GPA5_26") (pintype "unspecified"))
    )
    (net (code "84") (name "Net-(MCP5-GPA6)") (class "Default")
      (node (ref "GPIO5B/A") (pin "14") (pinfunction "14_14") (pintype "input"))
      (node (ref "MCP5") (pin "27") (pinfunction "GPA6_27") (pintype "unspecified"))
    )
    (net (code "85") (name "Net-(MCP5-GPA7)") (class "Default")
      (node (ref "GPIO5B/A") (pin "16") (pinfunction "16_16") (pintype "input"))
      (node (ref "MCP5") (pin "28") (pinfunction "GPA7_28") (pintype "unspecified"))
    )
    (net (code "86") (name "Net-(MCP5-GPB0)") (class "Default")
      (node (ref "GPIO5B/A") (pin "1") (pinfunction "1_1") (pintype "input"))
      (node (ref "MCP5") (pin "1") (pinfunction "GPB0_1") (pintype "unspecified"))
    )
    (net (code "87") (name "Net-(MCP5-GPB1)") (class "Default")
      (node (ref "GPIO5B/A") (pin "3") (pinfunction "3_3") (pintype "input"))
      (node (ref "MCP5") (pin "2") (pinfunction "GPB1_2") (pintype "unspecified"))
    )
    (net (code "88") (name "Net-(MCP5-GPB2)") (class "Default")
      (node (ref "GPIO5B/A") (pin "5") (pinfunction "5_5") (pintype "input"))
      (node (ref "MCP5") (pin "3") (pinfunction "GPB2_3") (pintype "unspecified"))
    )
    (net (code "89") (name "Net-(MCP5-GPB3)") (class "Default")
      (node (ref "GPIO5B/A") (pin "7") (pinfunction "7_7") (pintype "input"))
      (node (ref "MCP5") (pin "4") (pinfunction "GPB3_4") (pintype "unspecified"))
    )
    (net (code "90") (name "Net-(MCP5-GPB4)") (class "Default")
      (node (ref "GPIO5B/A") (pin "9") (pinfunction "9_9") (pintype "input"))
      (node (ref "MCP5") (pin "5") (pinfunction "GPB4_5") (pintype "unspecified"))
    )
    (net (code "91") (name "Net-(MCP5-GPB5)") (class "Default")
      (node (ref "GPIO5B/A") (pin "11") (pinfunction "11_11") (pintype "input"))
      (node (ref "MCP5") (pin "6") (pinfunction "GPB5_6") (pintype "unspecified"))
    )
    (net (code "92") (name "Net-(MCP5-GPB6)") (class "Default")
      (node (ref "GPIO5B/A") (pin "13") (pinfunction "13_13") (pintype "input"))
      (node (ref "MCP5") (pin "7") (pinfunction "GPB6_7") (pintype "unspecified"))
    )
    (net (code "93") (name "Net-(MCP5-GPB7)") (class "Default")
      (node (ref "GPIO5B/A") (pin "15") (pinfunction "15_15") (pintype "input"))
      (node (ref "MCP5") (pin "8") (pinfunction "GPB7_8") (pintype "unspecified"))
    )
    (net (code "94") (name "Net-(MCP5-INTA)") (class "Default")
      (node (ref "INTA/B") (pin "9") (pinfunction "9_9") (pintype "input"))
      (node (ref "MCP5") (pin "20") (pinfunction "INTA_20") (pintype "unspecified"))
    )
    (net (code "95") (name "Net-(MCP5-INTB)") (class "Default")
      (node (ref "INTA/B") (pin "10") (pinfunction "10_10") (pintype "input"))
      (node (ref "MCP5") (pin "19") (pinfunction "INTB_19") (pintype "unspecified"))
    )
    (net (code "96") (name "Net-(MCP6-GPA0)") (class "Default")
      (node (ref "GPIO6B/A") (pin "2") (pinfunction "2_2") (pintype "input"))
      (node (ref "MCP6") (pin "21") (pinfunction "GPA0_21") (pintype "unspecified"))
    )
    (net (code "97") (name "Net-(MCP6-GPA1)") (class "Default")
      (node (ref "GPIO6B/A") (pin "4") (pinfunction "4_4") (pintype "input"))
      (node (ref "MCP6") (pin "22") (pinfunction "GPA1_22") (pintype "unspecified"))
    )
    (net (code "98") (name "Net-(MCP6-GPA2)") (class "Default")
      (node (ref "GPIO6B/A") (pin "6") (pinfunction "6_6") (pintype "input"))
      (node (ref "MCP6") (pin "23") (pinfunction "GPA2_23") (pintype "unspecified"))
    )
    (net (code "99") (name "Net-(MCP6-GPA3)") (class "Default")
      (node (ref "GPIO6B/A") (pin "8") (pinfunction "8_8") (pintype "input"))
      (node (ref "MCP6") (pin "24") (pinfunction "GPA3_24") (pintype "unspecified"))
    )
    (net (code "100") (name "Net-(MCP6-GPA4)") (class "Default")
      (node (ref "GPIO6B/A") (pin "10") (pinfunction "10_10") (pintype "input"))
      (node (ref "MCP6") (pin "25") (pinfunction "GPA4_25") (pintype "unspecified"))
    )
    (net (code "101") (name "Net-(MCP6-GPA5)") (class "Default")
      (node (ref "GPIO6B/A") (pin "12") (pinfunction "12_12") (pintype "input"))
      (node (ref "MCP6") (pin "26") (pinfunction "GPA5_26") (pintype "unspecified"))
    )
    (net (code "102") (name "Net-(MCP6-GPA6)") (class "Default")
      (node (ref "GPIO6B/A") (pin "14") (pinfunction "14_14") (pintype "input"))
      (node (ref "MCP6") (pin "27") (pinfunction "GPA6_27") (pintype "unspecified"))
    )
    (net (code "103") (name "Net-(MCP6-GPA7)") (class "Default")
      (node (ref "GPIO6B/A") (pin "16") (pinfunction "16_16") (pintype "input"))
      (node (ref "MCP6") (pin "28") (pinfunction "GPA7_28") (pintype "unspecified"))
    )
    (net (code "104") (name "Net-(MCP6-GPB0)") (class "Default")
      (node (ref "GPIO6B/A") (pin "1") (pinfunction "1_1") (pintype "input"))
      (node (ref "MCP6") (pin "1") (pinfunction "GPB0_1") (pintype "unspecified"))
    )
    (net (code "105") (name "Net-(MCP6-GPB1)") (class "Default")
      (node (ref "GPIO6B/A") (pin "3") (pinfunction "3_3") (pintype "input"))
      (node (ref "MCP6") (pin "2") (pinfunction "GPB1_2") (pintype "unspecified"))
    )
    (net (code "106") (name "Net-(MCP6-GPB2)") (class "Default")
      (node (ref "GPIO6B/A") (pin "5") (pinfunction "5_5") (pintype "input"))
      (node (ref "MCP6") (pin "3") (pinfunction "GPB2_3") (pintype "unspecified"))
    )
    (net (code "107") (name "Net-(MCP6-GPB3)") (class "Default")
      (node (ref "GPIO6B/A") (pin "7") (pinfunction "7_7") (pintype "input"))
      (node (ref "MCP6") (pin "4") (pinfunction "GPB3_4") (pintype "unspecified"))
    )
    (net (code "108") (name "Net-(MCP6-GPB4)") (class "Default")
      (node (ref "GPIO6B/A") (pin "9") (pinfunction "9_9") (pintype "input"))
      (node (ref "MCP6") (pin "5") (pinfunction "GPB4_5") (pintype "unspecified"))
    )
    (net (code "109") (name "Net-(MCP6-GPB5)") (class "Default")
      (node (ref "GPIO6B/A") (pin "11") (pinfunction "11_11") (pintype "input"))
      (node (ref "MCP6") (pin "6") (pinfunction "GPB5_6") (pintype "unspecified"))
    )
    (net (code "110") (name "Net-(MCP6-GPB6)") (class "Default")
      (node (ref "GPIO6B/A") (pin "13") (pinfunction "13_13") (pintype "input"))
      (node (ref "MCP6") (pin "7") (pinfunction "GPB6_7") (pintype "unspecified"))
    )
    (net (code "111") (name "Net-(MCP6-GPB7)") (class "Default")
      (node (ref "GPIO6B/A") (pin "15") (pinfunction "15_15") (pintype "input"))
      (node (ref "MCP6") (pin "8") (pinfunction "GPB7_8") (pintype "unspecified"))
    )
    (net (code "112") (name "Net-(MCP6-INTA)") (class "Default")
      (node (ref "INTA/B") (pin "11") (pinfunction "11_11") (pintype "input"))
      (node (ref "MCP6") (pin "20") (pinfunction "INTA_20") (pintype "unspecified"))
    )
    (net (code "113") (name "Net-(MCP6-INTB)") (class "Default")
      (node (ref "INTA/B") (pin "12") (pinfunction "12_12") (pintype "input"))
      (node (ref "MCP6") (pin "19") (pinfunction "INTB_19") (pintype "unspecified"))
    )
    (net (code "114") (name "Net-(MCP7-GPA0)") (class "Default")
      (node (ref "GPIO7B/A") (pin "2") (pinfunction "2_2") (pintype "input"))
      (node (ref "MCP7") (pin "21") (pinfunction "GPA0_21") (pintype "unspecified"))
    )
    (net (code "115") (name "Net-(MCP7-GPA1)") (class "Default")
      (node (ref "GPIO7B/A") (pin "4") (pinfunction "4_4") (pintype "input"))
      (node (ref "MCP7") (pin "22") (pinfunction "GPA1_22") (pintype "unspecified"))
    )
    (net (code "116") (name "Net-(MCP7-GPA2)") (class "Default")
      (node (ref "GPIO7B/A") (pin "6") (pinfunction "6_6") (pintype "input"))
      (node (ref "MCP7") (pin "23") (pinfunction "GPA2_23") (pintype "unspecified"))
    )
    (net (code "117") (name "Net-(MCP7-GPA3)") (class "Default")
      (node (ref "GPIO7B/A") (pin "8") (pinfunction "8_8") (pintype "input"))
      (node (ref "MCP7") (pin "24") (pinfunction "GPA3_24") (pintype "unspecified"))
    )
    (net (code "118") (name "Net-(MCP7-GPA4)") (class "Default")
      (node (ref "GPIO7B/A") (pin "10") (pinfunction "10_10") (pintype "input"))
      (node (ref "MCP7") (pin "25") (pinfunction "GPA4_25") (pintype "unspecified"))
    )
    (net (code "119") (name "Net-(MCP7-GPA5)") (class "Default")
      (node (ref "GPIO7B/A") (pin "12") (pinfunction "12_12") (pintype "input"))
      (node (ref "MCP7") (pin "26") (pinfunction "GPA5_26") (pintype "unspecified"))
    )
    (net (code "120") (name "Net-(MCP7-GPA6)") (class "Default")
      (node (ref "GPIO7B/A") (pin "14") (pinfunction "14_14") (pintype "input"))
      (node (ref "MCP7") (pin "27") (pinfunction "GPA6_27") (pintype "unspecified"))
    )
    (net (code "121") (name "Net-(MCP7-GPA7)") (class "Default")
      (node (ref "GPIO7B/A") (pin "16") (pinfunction "16_16") (pintype "input"))
      (node (ref "MCP7") (pin "28") (pinfunction "GPA7_28") (pintype "unspecified"))
    )
    (net (code "122") (name "Net-(MCP7-GPB0)") (class "Default")
      (node (ref "GPIO7B/A") (pin "1") (pinfunction "1_1") (pintype "input"))
      (node (ref "MCP7") (pin "1") (pinfunction "GPB0_1") (pintype "unspecified"))
    )
    (net (code "123") (name "Net-(MCP7-GPB1)") (class "Default")
      (node (ref "GPIO7B/A") (pin "3") (pinfunction "3_3") (pintype "input"))
      (node (ref "MCP7") (pin "2") (pinfunction "GPB1_2") (pintype "unspecified"))
    )
    (net (code "124") (name "Net-(MCP7-GPB2)") (class "Default")
      (node (ref "GPIO7B/A") (pin "5") (pinfunction "5_5") (pintype "input"))
      (node (ref "MCP7") (pin "3") (pinfunction "GPB2_3") (pintype "unspecified"))
    )
    (net (code "125") (name "Net-(MCP7-GPB3)") (class "Default")
      (node (ref "GPIO7B/A") (pin "7") (pinfunction "7_7") (pintype "input"))
      (node (ref "MCP7") (pin "4") (pinfunction "GPB3_4") (pintype "unspecified"))
    )
    (net (code "126") (name "Net-(MCP7-GPB4)") (class "Default")
      (node (ref "GPIO7B/A") (pin "9") (pinfunction "9_9") (pintype "input"))
      (node (ref "MCP7") (pin "5") (pinfunction "GPB4_5") (pintype "unspecified"))
    )
    (net (code "127") (name "Net-(MCP7-GPB5)") (class "Default")
      (node (ref "GPIO7B/A") (pin "11") (pinfunction "11_11") (pintype "input"))
      (node (ref "MCP7") (pin "6") (pinfunction "GPB5_6") (pintype "unspecified"))
    )
    (net (code "128") (name "Net-(MCP7-GPB6)") (class "Default")
      (node (ref "GPIO7B/A") (pin "13") (pinfunction "13_13") (pintype "input"))
      (node (ref "MCP7") (pin "7") (pinfunction "GPB6_7") (pintype "unspecified"))
    )
    (net (code "129") (name "Net-(MCP7-GPB7)") (class "Default")
      (node (ref "GPIO7B/A") (pin "15") (pinfunction "15_15") (pintype "input"))
      (node (ref "MCP7") (pin "8") (pinfunction "GPB7_8") (pintype "unspecified"))
    )
    (net (code "130") (name "Net-(MCP7-INTA)") (class "Default")
      (node (ref "INTA/B") (pin "13") (pinfunction "13_13") (pintype "input"))
      (node (ref "MCP7") (pin "20") (pinfunction "INTA_20") (pintype "unspecified"))
    )
    (net (code "131") (name "Net-(MCP7-INTB)") (class "Default")
      (node (ref "INTA/B") (pin "14") (pinfunction "14_14") (pintype "input"))
      (node (ref "MCP7") (pin "19") (pinfunction "INTB_19") (pintype "unspecified"))
    )
    (net (code "132") (name "Net-(MCP8-GPA0)") (class "Default")
      (node (ref "GPIO8B/A") (pin "2") (pinfunction "2_2") (pintype "input"))
      (node (ref "MCP8") (pin "21") (pinfunction "GPA0_21") (pintype "unspecified"))
    )
    (net (code "133") (name "Net-(MCP8-GPA1)") (class "Default")
      (node (ref "GPIO8B/A") (pin "4") (pinfunction "4_4") (pintype "input"))
      (node (ref "MCP8") (pin "22") (pinfunction "GPA1_22") (pintype "unspecified"))
    )
    (net (code "134") (name "Net-(MCP8-GPA2)") (class "Default")
      (node (ref "GPIO8B/A") (pin "6") (pinfunction "6_6") (pintype "input"))
      (node (ref "MCP8") (pin "23") (pinfunction "GPA2_23") (pintype "unspecified"))
    )
    (net (code "135") (name "Net-(MCP8-GPA3)") (class "Default")
      (node (ref "GPIO8B/A") (pin "8") (pinfunction "8_8") (pintype "input"))
      (node (ref "MCP8") (pin "24") (pinfunction "GPA3_24") (pintype "unspecified"))
    )
    (net (code "136") (name "Net-(MCP8-GPA4)") (class "Default")
      (node (ref "GPIO8B/A") (pin "10") (pinfunction "10_10") (pintype "input"))
      (node (ref "MCP8") (pin "25") (pinfunction "GPA4_25") (pintype "unspecified"))
    )
    (net (code "137") (name "Net-(MCP8-GPA5)") (class "Default")
      (node (ref "GPIO8B/A") (pin "12") (pinfunction "12_12") (pintype "input"))
      (node (ref "MCP8") (pin "26") (pinfunction "GPA5_26") (pintype "unspecified"))
    )
    (net (code "138") (name "Net-(MCP8-GPA6)") (class "Default")
      (node (ref "GPIO8B/A") (pin "14") (pinfunction "14_14") (pintype "input"))
      (node (ref "MCP8") (pin "27") (pinfunction "GPA6_27") (pintype "unspecified"))
    )
    (net (code "139") (name "Net-(MCP8-GPA7)") (class "Default")
      (node (ref "GPIO8B/A") (pin "16") (pinfunction "16_16") (pintype "input"))
      (node (ref "MCP8") (pin "28") (pinfunction "GPA7_28") (pintype "unspecified"))
    )
    (net (code "140") (name "Net-(MCP8-GPB0)") (class "Default")
      (node (ref "GPIO8B/A") (pin "1") (pinfunction "1_1") (pintype "input"))
      (node (ref "MCP8") (pin "1") (pinfunction "GPB0_1") (pintype "unspecified"))
    )
    (net (code "141") (name "Net-(MCP8-GPB1)") (class "Default")
      (node (ref "GPIO8B/A") (pin "3") (pinfunction "3_3") (pintype "input"))
      (node (ref "MCP8") (pin "2") (pinfunction "GPB1_2") (pintype "unspecified"))
    )
    (net (code "142") (name "Net-(MCP8-GPB2)") (class "Default")
      (node (ref "GPIO8B/A") (pin "5") (pinfunction "5_5") (pintype "input"))
      (node (ref "MCP8") (pin "3") (pinfunction "GPB2_3") (pintype "unspecified"))
    )
    (net (code "143") (name "Net-(MCP8-GPB3)") (class "Default")
      (node (ref "GPIO8B/A") (pin "7") (pinfunction "7_7") (pintype "input"))
      (node (ref "MCP8") (pin "4") (pinfunction "GPB3_4") (pintype "unspecified"))
    )
    (net (code "144") (name "Net-(MCP8-GPB4)") (class "Default")
      (node (ref "GPIO8B/A") (pin "9") (pinfunction "9_9") (pintype "input"))
      (node (ref "MCP8") (pin "5") (pinfunction "GPB4_5") (pintype "unspecified"))
    )
    (net (code "145") (name "Net-(MCP8-GPB5)") (class "Default")
      (node (ref "GPIO8B/A") (pin "11") (pinfunction "11_11") (pintype "input"))
      (node (ref "MCP8") (pin "6") (pinfunction "GPB5_6") (pintype "unspecified"))
    )
    (net (code "146") (name "Net-(MCP8-GPB6)") (class "Default")
      (node (ref "GPIO8B/A") (pin "13") (pinfunction "13_13") (pintype "input"))
      (node (ref "MCP8") (pin "7") (pinfunction "GPB6_7") (pintype "unspecified"))
    )
    (net (code "147") (name "Net-(MCP8-GPB7)") (class "Default")
      (node (ref "GPIO8B/A") (pin "15") (pinfunction "15_15") (pintype "input"))
      (node (ref "MCP8") (pin "8") (pinfunction "GPB7_8") (pintype "unspecified"))
    )
    (net (code "148") (name "Net-(MCP8-INTA)") (class "Default")
      (node (ref "INTA/B") (pin "15") (pinfunction "15_15") (pintype "input"))
      (node (ref "MCP8") (pin "20") (pinfunction "INTA_20") (pintype "unspecified"))
    )
    (net (code "149") (name "Net-(MCP8-INTB)") (class "Default")
      (node (ref "INTA/B") (pin "16") (pinfunction "16_16") (pintype "input"))
      (node (ref "MCP8") (pin "19") (pinfunction "INTB_19") (pintype "unspecified"))
    )
    (net (code "150") (name "unconnected-(MCP1-NC-Pad11)") (class "Default")
      (node (ref "MCP1") (pin "11") (pinfunction "NC_11") (pintype "unspecified"))
    )
    (net (code "151") (name "unconnected-(MCP1-NC-Pad14)") (class "Default")
      (node (ref "MCP1") (pin "14") (pinfunction "NC_14") (pintype "unspecified"))
    )
    (net (code "152") (name "unconnected-(MCP2-NC-Pad11)") (class "Default")
      (node (ref "MCP2") (pin "11") (pinfunction "NC_11") (pintype "unspecified"))
    )
    (net (code "153") (name "unconnected-(MCP2-NC-Pad14)") (class "Default")
      (node (ref "MCP2") (pin "14") (pinfunction "NC_14") (pintype "unspecified"))
    )
    (net (code "154") (name "unconnected-(MCP3-NC-Pad11)") (class "Default")
      (node (ref "MCP3") (pin "11") (pinfunction "NC_11") (pintype "unspecified"))
    )
    (net (code "155") (name "unconnected-(MCP3-NC-Pad14)") (class "Default")
      (node (ref "MCP3") (pin "14") (pinfunction "NC_14") (pintype "unspecified"))
    )
    (net (code "156") (name "unconnected-(MCP4-NC-Pad11)") (class "Default")
      (node (ref "MCP4") (pin "11") (pinfunction "NC_11") (pintype "unspecified"))
    )
    (net (code "157") (name "unconnected-(MCP4-NC-Pad14)") (class "Default")
      (node (ref "MCP4") (pin "14") (pinfunction "NC_14") (pintype "unspecified"))
    )
    (net (code "158") (name "unconnected-(MCP5-NC-Pad11)") (class "Default")
      (node (ref "MCP5") (pin "11") (pinfunction "NC_11") (pintype "unspecified"))
    )
    (net (code "159") (name "unconnected-(MCP5-NC-Pad14)") (class "Default")
      (node (ref "MCP5") (pin "14") (pinfunction "NC_14") (pintype "unspecified"))
    )
    (net (code "160") (name "unconnected-(MCP6-NC-Pad11)") (class "Default")
      (node (ref "MCP6") (pin "11") (pinfunction "NC_11") (pintype "unspecified"))
    )
    (net (code "161") (name "unconnected-(MCP6-NC-Pad14)") (class "Default")
      (node (ref "MCP6") (pin "14") (pinfunction "NC_14") (pintype "unspecified"))
    )
    (net (code "162") (name "unconnected-(MCP7-NC-Pad11)") (class "Default")
      (node (ref "MCP7") (pin "11") (pinfunction "NC_11") (pintype "unspecified"))
    )
    (net (code "163") (name "unconnected-(MCP7-NC-Pad14)") (class "Default")
      (node (ref "MCP7") (pin "14") (pinfunction "NC_14") (pintype "unspecified"))
    )
    (net (code "164") (name "unconnected-(MCP8-NC-Pad11)") (class "Default")
      (node (ref "MCP8") (pin "11") (pinfunction "NC_11") (pintype "unspecified"))
    )
    (net (code "165") (name "unconnected-(MCP8-NC-Pad14)") (class "Default")
      (node (ref "MCP8") (pin "14") (pinfunction "NC_14") (pintype "unspecified"))
    )
    (net (code "166") (name "unconnected-(USB_TO_TTL-RXD-Pad3)") (class "Default")
      (node (ref "USB_TO_TTL") (pin "3") (pinfunction "RXD_3") (pintype "input"))
    )
    (net (code "167") (name "unconnected-(USB_TO_TTL-RXD-Pad4)") (class "Default")
      (node (ref "USB_TO_TTL") (pin "4") (pinfunction "RXD_4") (pintype "input"))
    )
    (net (code "168") (name "unconnected-(USB_TO_TTL-TXD-Pad5)") (class "Default")
      (node (ref "USB_TO_TTL") (pin "5") (pinfunction "TXD_5") (pintype "input"))
    )
    (net (code "169") (name "unconnected-(USB_TO_TTL-TXD-Pad6)") (class "Default")
      (node (ref "USB_TO_TTL") (pin "6") (pinfunction "TXD_6") (pintype "input"))
    )
    (net (code "170") (name "unconnected-(USB_TO_TTL-VCC-Pad9)") (class "Default")
      (node (ref "USB_TO_TTL") (pin "9") (pinfunction "VCC_9") (pintype "input"))
    )
    (net (code "171") (name "unconnected-(USB_TO_TTL-VCC-Pad10)") (class "Default")
      (node (ref "USB_TO_TTL") (pin "10") (pinfunction "VCC_10") (pintype "input"))
    )
  )
)
